# 02-Mezzanine.net
KiCad netlist of a schematic drawn in Altium Designer
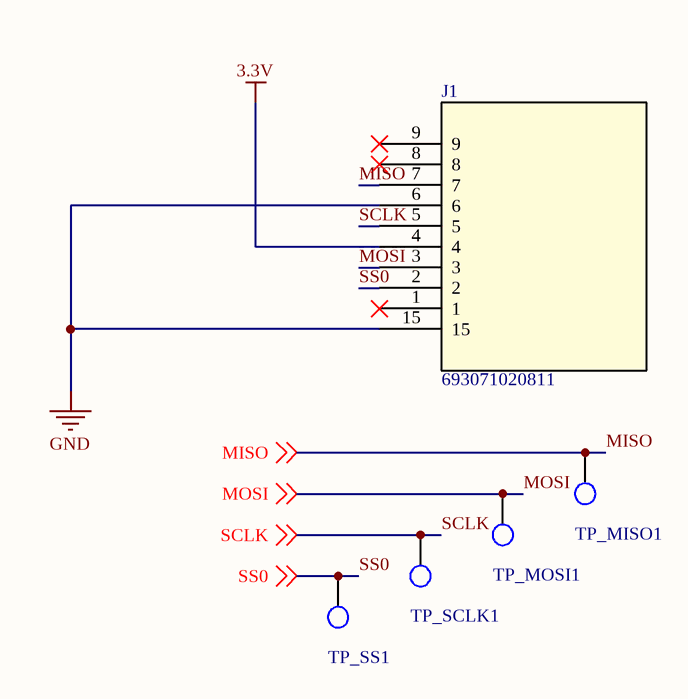
[diagram p0: 02-Mezzanine.SchDoc]

(export (version "E")
  (design (tool "Eeschema 10.0.6"))
  (components
    (comp (ref "J1")
      (value "693071020811")
      (footprint "CONN9_020811_WRE")
      (description "No Description Available")
      (fields (field (name "COPYRIGHT") "Copyright (C) 2022 Ultra Librarian. All rights reserved."))
      (libsource (lib "693071020811") (part "693071020811"))
    )
    (comp (ref "TP_MISO1")
      (value "TP_1206")
      (footprint "TP-SMC-1206")
      (description "Test Point SMD 1206")
      (fields
        (field (name "MANUFACTURER") "TE Connectivity (Tyco Electronics)")
        (field (name "MANUFACTURER PART NUMBER") "1625854-1")
      )
      (libsource (lib "ECE453-F22-Power") (part "TP_1206"))
    )
    (comp (ref "TP_MOSI1")
      (value "TP_1206")
      (footprint "TP-SMC-1206")
      (description "Test Point SMD 1206")
      (fields
        (field (name "MANUFACTURER") "TE Connectivity (Tyco Electronics)")
        (field (name "MANUFACTURER PART NUMBER") "1625854-1")
      )
      (libsource (lib "ECE453-F22-Power") (part "TP_1206"))
    )
    (comp (ref "TP_SCLK1")
      (value "TP_1206")
      (footprint "TP-SMC-1206")
      (description "Test Point SMD 1206")
      (fields
        (field (name "MANUFACTURER") "TE Connectivity (Tyco Electronics)")
        (field (name "MANUFACTURER PART NUMBER") "1625854-1")
      )
      (libsource (lib "ECE453-F22-Power") (part "TP_1206"))
    )
    (comp (ref "TP_SS1")
      (value "TP_1206")
      (footprint "TP-SMC-1206")
      (description "Test Point SMD 1206")
      (fields
        (field (name "MANUFACTURER") "TE Connectivity (Tyco Electronics)")
        (field (name "MANUFACTURER PART NUMBER") "1625854-1")
      )
      (libsource (lib "ECE453-F22-Power") (part "TP_1206"))
    )
  )
  (nets
    (net (code "1") (name "3.3V") (class "Default")
      (node (ref "J1") (pin "4") (pinfunction "4_4") (pintype "passive"))
    )
    (net (code "2") (name "GND") (class "Default")
      (node (ref "J1") (pin "15") (pinfunction "15_15") (pintype "passive"))
      (node (ref "J1") (pin "6") (pinfunction "6_6") (pintype "passive"))
    )
    (net (code "3") (name "MISO") (class "Default")
      (node (ref "J1") (pin "7") (pinfunction "7_7") (pintype "passive"))
      (node (ref "TP_MISO1") (pin "1") (pintype "passive"))
    )
    (net (code "4") (name "MOSI") (class "Default")
      (node (ref "J1") (pin "3") (pinfunction "3_3") (pintype "passive"))
      (node (ref "TP_MOSI1") (pin "1") (pintype "passive"))
    )
    (net (code "5") (name "SCLK") (class "Default")
      (node (ref "J1") (pin "5") (pinfunction "5_5") (pintype "passive"))
      (node (ref "TP_SCLK1") (pin "1") (pintype "passive"))
    )
    (net (code "6") (name "SS0") (class "Default")
      (node (ref "J1") (pin "2") (pinfunction "2_2") (pintype "passive"))
      (node (ref "TP_SS1") (pin "1") (pintype "passive"))
    )
    (net (code "7") (name "unconnected-(J1-Pad1)") (class "Default")
      (node (ref "J1") (pin "1") (pinfunction "1_1") (pintype "passive+no_connect"))
    )
    (net (code "8") (name "unconnected-(J1-Pad8)") (class "Default")
      (node (ref "J1") (pin "8") (pinfunction "8_8") (pintype "passive+no_connect"))
    )
    (net (code "9") (name "unconnected-(J1-Pad9)") (class "Default")
      (node (ref "J1") (pin "9") (pinfunction "9_9") (pintype "passive+no_connect"))
    )
  )
)
